# GPS.net
KiCad netlist of a schematic drawn in Altium Designer
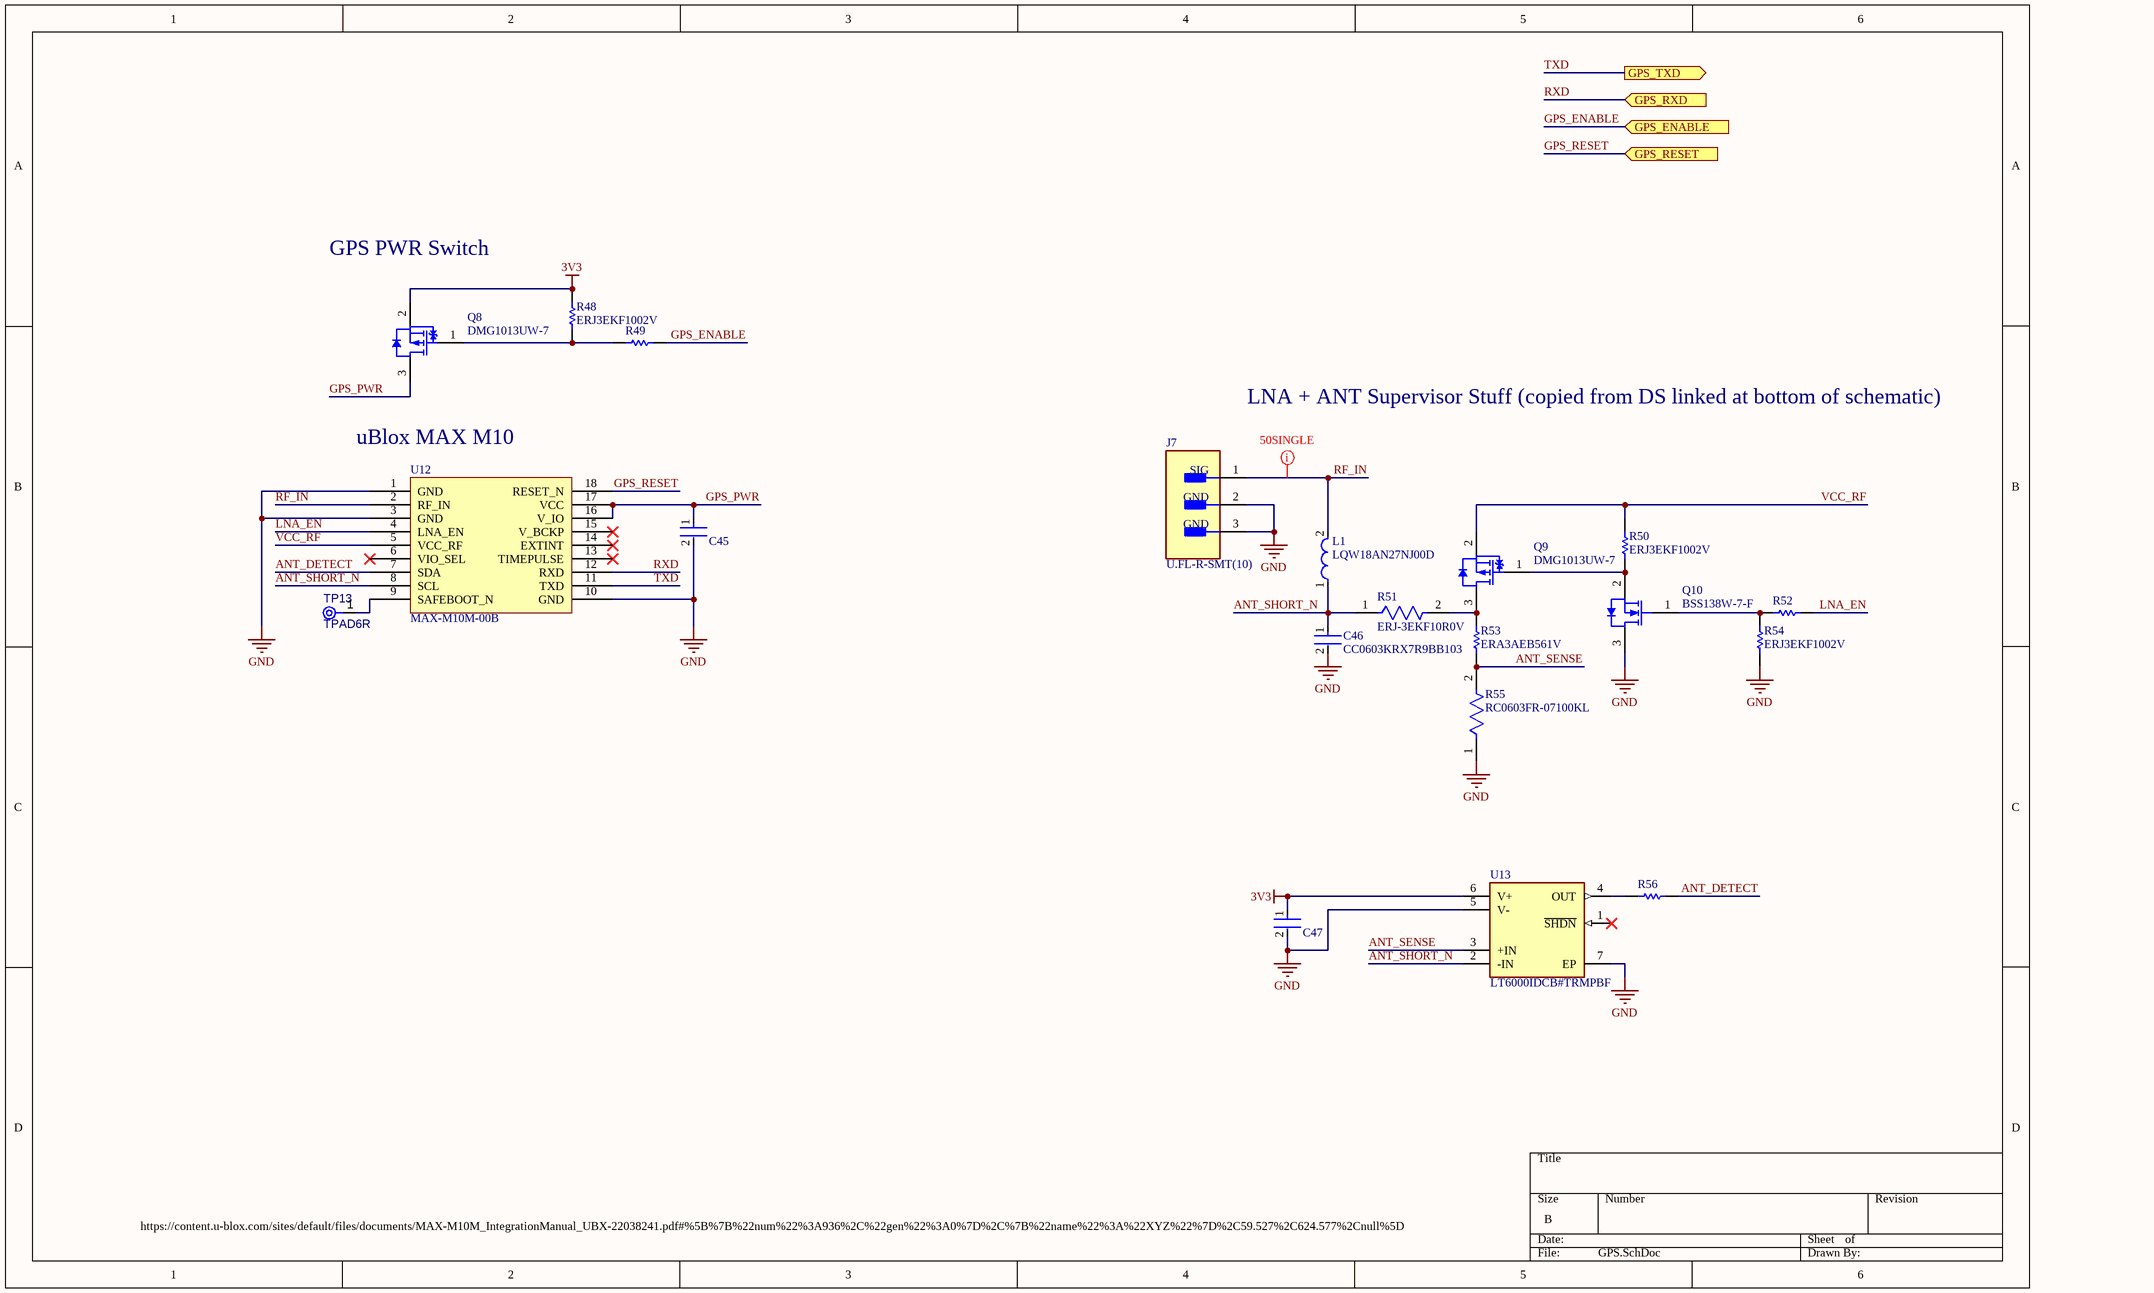
[diagram p0: GPS.SchDoc]

(export (version "E")
  (design (tool "Eeschema 10.0.6"))
  (components
    (comp (ref "C45")
      (value "C0402C104K8PACTU")
      (footprint "FP-C0402-BB-MFG")
      (description "CAP CER 0.1UF 10V X5R 0402")
      (fields (field (name "MANUFACTURER") "Kemet") (field (name "TOLERANCE") "0.1"))
      (libsource (lib "Altium Content Vault") (part "b4654b650e69147ec39a6b967a45e02"))
    )
    (comp (ref "C46")
      (value "CC0603KRX7R9BB103")
      (footprint "FP-CC0603-DA-MFG")
      (description "CAP CER 10000PF 50V X7R 0603")
      (fields (field (name "TOLERANCE") "0.1") (field (name "MANUFACTURER") "YAGEO"))
      (libsource (lib "Altium Content Vault") (part "11868f565c42a9108669ba33697ecf6"))
    )
    (comp (ref "C47")
      (value "C0402C104K8PACTU")
      (footprint "FP-C0402-BB-MFG")
      (description "CAP CER 0.1UF 10V X5R 0402")
      (fields (field (name "MANUFACTURER") "Kemet") (field (name "TOLERANCE") "0.1"))
      (libsource (lib "Altium Content Vault") (part "b4654b650e69147ec39a6b967a45e02"))
    )
    (comp (ref "J7")
      (value "U.FL-R-SMT(10)")
      (footprint "FP-U_FL-R-SMT_10-MFG")
      (description "CONN U.FL RCPT STR 50 OHM SMD")
      (libsource (lib "Altium Content Vault") (part "eef6fde44c591823e8076210edfe12f"))
    )
    (comp (ref "L1")
      (value "LQW18AN27NJ00D")
      (footprint "FP-LQW18AN_00-MFG")
      (description "Wire Wound RF Inductor 27nH ±5% 440mA 0.21Ω 0603 (1608)")
      (fields (field (name "TOLERANCE") "5%"))
      (libsource (lib "Altium Content Vault") (part "725321dda6339637d4d059423bc1c3c"))
    )
    (comp (ref "Q8")
      (value "DMG1013UW-7")
      (footprint "DIOD-SOT323-3_V")
      (fields (field (name "MANUFACTURER") "Diodes Inc"))
      (libsource (lib "Altium Content Vault") (part "PEMOS-GSD-3_C"))
    )
    (comp (ref "Q9")
      (value "DMG1013UW-7")
      (footprint "DIOD-SOT323-3_V")
      (fields (field (name "MANUFACTURER") "Diodes Inc"))
      (libsource (lib "Altium Content Vault") (part "PEMOS-GSD-3_C"))
    )
    (comp (ref "Q10")
      (value "BSS138W-7-F")
      (footprint "DIOD-SOT323-3_V")
      (fields (field (name "MANUFACTURER") "DiodesIncorporated"))
      (libsource (lib "Altium Content Vault") (part "NEMOS-GSD-3"))
    )
    (comp (ref "R48")
      (value "ERJ3EKF1002V")
      (footprint "RESC1609X55X30LL15T15")
      (description "Chip Resistor, 10 KOhm, +/- 1%, 0.1 W, -55 to 155 degC, 0603 (1608 Metric), RoHS, Tape and Reel")
      (fields (field (name "TOLERANCE") "1%") (field (name "MANUFACTURER") "Panasonic"))
      (libsource (lib "Altium Content Vault") (part "RES-2"))
    )
    (comp (ref "R49")
      (value "ERJ-3EKF1001V")
      (footprint "RESC1608X55X30LL15T15")
      (fields (field (name "MANUFACTURER") "Panasonic"))
      (libsource (lib "Altium Content Vault") (part "RES"))
    )
    (comp (ref "R50")
      (value "ERJ3EKF1002V")
      (footprint "RESC1609X55X30LL15T15")
      (description "Chip Resistor, 10 KOhm, +/- 1%, 0.1 W, -55 to 155 degC, 0603 (1608 Metric), RoHS, Tape and Reel")
      (fields (field (name "TOLERANCE") "1%") (field (name "MANUFACTURER") "Panasonic"))
      (libsource (lib "Altium Content Vault") (part "RES-2"))
    )
    (comp (ref "R51")
      (value "ERJ-3EKF10R0V")
      (footprint "FP-ERJ3EK-MFG")
      (description "RES SMD 10 OHM 1% 1/10W 0603")
      (fields
        (field (name "OCTOPART") "https://octopart.com/erj-3ekf10r0v-panasonic-55403649")
        (field (name "MANUFACTURER") "Panasonic")
      )
      (libsource (lib "Altium Content Vault") (part "1029c3af85768c4190bb7ad29bc67b5"))
    )
    (comp (ref "R52")
      (value "ERJ-3EKF1001V")
      (footprint "RESC1608X55X30LL15T15")
      (fields (field (name "MANUFACTURER") "Panasonic"))
      (libsource (lib "Altium Content Vault") (part "RES"))
    )
    (comp (ref "R53")
      (value "ERA3AEB561V")
      (footprint "RESC1608X55X30LL20T20")
      (fields (field (name "MANUFACTURER") "Panasonic"))
      (libsource (lib "Altium Content Vault") (part "RES"))
    )
    (comp (ref "R54")
      (value "ERJ3EKF1002V")
      (footprint "RESC1609X55X30LL15T15")
      (description "Chip Resistor, 10 KOhm, +/- 1%, 0.1 W, -55 to 155 degC, 0603 (1608 Metric), RoHS, Tape and Reel")
      (fields (field (name "TOLERANCE") "1%") (field (name "MANUFACTURER") "Panasonic"))
      (libsource (lib "Altium Content Vault") (part "RES-2"))
    )
    (comp (ref "R55")
      (value "RC0603FR-07100KL")
      (footprint "FP-RC0603-0_55-MFG")
      (description "RES SMD 100K OHM 1% 1/10W 0603")
      (fields (field (name "TOLERANCE") "1%"))
      (libsource (lib "Altium Content Vault") (part "1029c3af85768c4190bb7ad29bc67b5"))
    )
    (comp (ref "R56")
      (value "ERJ-3EKF1001V")
      (footprint "RESC1608X55X30LL15T15")
      (fields (field (name "MANUFACTURER") "Panasonic"))
      (libsource (lib "Altium Content Vault") (part "RES"))
    )
    (comp (ref "TP13")
      (value "TPAD6R")
      (footprint "TP06R")
      (description "0.6mm round")
      (libsource (lib "uORocketry Hardware") (part "CMP-001-0001-4"))
    )
    (comp (ref "U12")
      (value "MAX-M10M-00B")
      (footprint "MAX-M10M-00B-Footprint-1")
      (description "Gnss Lcc Rx Mod, Rom, Crystal")
      (libsource (lib "Space Concordia") (part "MAX-M10M-00B"))
    )
    (comp (ref "U13")
      (value "LT6000IDCB#TRMPBF")
      (footprint "FP-DCB-6-05-08-1715-MFG")
      (description "IC OPAMP GP 1 CIRCUIT 6DFN")
      (libsource (lib "Altium Content Vault") (part "33bb285994f2e703f79bf9d86341a8a"))
    )
  )
  (nets
    (net (code "1") (name "/ANT_DETECT") (class "Default")
      (node (ref "R56") (pin "1") (pinfunction "1_1") (pintype "passive"))
      (node (ref "U12") (pin "7") (pinfunction "SDA_7") (pintype "passive"))
    )
    (net (code "2") (name "/ANT_SENSE") (class "Default")
      (node (ref "R53") (pin "1") (pinfunction "1_1") (pintype "passive"))
      (node (ref "R55") (pin "2") (pinfunction "2_2") (pintype "passive"))
      (node (ref "U13") (pin "3") (pinfunction "+IN_3") (pintype "tri_state"))
    )
    (net (code "3") (name "/ANT_SHORT_N") (class "Default")
      (node (ref "C46") (pin "1") (pinfunction "1_1") (pintype "passive"))
      (node (ref "L1") (pin "1") (pinfunction "1_1") (pintype "passive"))
      (node (ref "R51") (pin "1") (pinfunction "1_1") (pintype "passive"))
      (node (ref "U12") (pin "8") (pinfunction "SCL_8") (pintype "passive"))
      (node (ref "U13") (pin "2") (pinfunction "-IN_2") (pintype "tri_state"))
    )
    (net (code "4") (name "/GPS_ENABLE") (class "Default")
      (node (ref "R49") (pin "1") (pinfunction "1_1") (pintype "passive"))
    )
    (net (code "5") (name "/GPS_PWR") (class "Default")
      (node (ref "C45") (pin "1") (pinfunction "1_1") (pintype "passive"))
      (node (ref "Q8") (pin "3") (pinfunction "D_3") (pintype "passive"))
      (node (ref "U12") (pin "16") (pinfunction "V_IO_16") (pintype "passive"))
      (node (ref "U12") (pin "17") (pinfunction "VCC_17") (pintype "passive"))
    )
    (net (code "6") (name "/GPS_RESET") (class "Default")
      (node (ref "U12") (pin "18") (pinfunction "RESET_N_18") (pintype "passive"))
    )
    (net (code "7") (name "/LNA_EN") (class "Default")
      (node (ref "R52") (pin "1") (pinfunction "1_1") (pintype "passive"))
      (node (ref "U12") (pin "4") (pinfunction "LNA_EN_4") (pintype "passive"))
    )
    (net (code "8") (name "/RF_IN") (class "Default")
      (node (ref "J7") (pin "1") (pinfunction "SIG_1") (pintype "passive"))
      (node (ref "L1") (pin "2") (pinfunction "2_2") (pintype "passive"))
      (node (ref "U12") (pin "2") (pinfunction "RF_IN_2") (pintype "passive"))
    )
    (net (code "9") (name "/RXD") (class "Default")
      (node (ref "U12") (pin "12") (pinfunction "RXD_12") (pintype "passive"))
    )
    (net (code "10") (name "/TXD") (class "Default")
      (node (ref "U12") (pin "11") (pinfunction "TXD_11") (pintype "passive"))
    )
    (net (code "11") (name "/VCC_RF") (class "Default")
      (node (ref "Q9") (pin "2") (pinfunction "S_2") (pintype "passive"))
      (node (ref "R50") (pin "2") (pinfunction "2_2") (pintype "passive"))
      (node (ref "U12") (pin "5") (pinfunction "VCC_RF_5") (pintype "passive"))
    )
    (net (code "12") (name "3V3") (class "Default")
      (node (ref "C47") (pin "1") (pinfunction "1_1") (pintype "passive"))
      (node (ref "Q8") (pin "2") (pinfunction "S_2") (pintype "passive"))
      (node (ref "R48") (pin "2") (pinfunction "2_2") (pintype "passive"))
      (node (ref "U13") (pin "6") (pinfunction "V+_6") (pintype "power_in"))
    )
    (net (code "13") (name "GND") (class "Default")
      (node (ref "C45") (pin "2") (pinfunction "2_2") (pintype "passive"))
      (node (ref "C46") (pin "2") (pinfunction "2_2") (pintype "passive"))
      (node (ref "C47") (pin "2") (pinfunction "2_2") (pintype "passive"))
      (node (ref "J7") (pin "2") (pinfunction "GND_2") (pintype "power_in"))
      (node (ref "J7") (pin "3") (pinfunction "GND_3") (pintype "power_in"))
      (node (ref "Q10") (pin "3") (pinfunction "D_3") (pintype "passive"))
      (node (ref "R54") (pin "1") (pinfunction "1_1") (pintype "passive"))
      (node (ref "R55") (pin "1") (pinfunction "1_1") (pintype "passive"))
      (node (ref "U12") (pin "1") (pinfunction "GND_1") (pintype "passive"))
      (node (ref "U12") (pin "10") (pinfunction "GND_10") (pintype "passive"))
      (node (ref "U12") (pin "3") (pinfunction "GND_3") (pintype "passive"))
      (node (ref "U13") (pin "5") (pinfunction "V-_5") (pintype "power_in"))
      (node (ref "U13") (pin "7") (pinfunction "EP_7") (pintype "power_in"))
    )
    (net (code "14") (name "Net-(Q8-G)") (class "Default")
      (node (ref "Q8") (pin "1") (pinfunction "G_1") (pintype "passive"))
      (node (ref "R48") (pin "1") (pinfunction "1_1") (pintype "passive"))
      (node (ref "R49") (pin "2") (pinfunction "2_2") (pintype "passive"))
    )
    (net (code "15") (name "Net-(Q9-D)") (class "Default")
      (node (ref "Q9") (pin "3") (pinfunction "D_3") (pintype "passive"))
      (node (ref "R51") (pin "2") (pinfunction "2_2") (pintype "passive"))
      (node (ref "R53") (pin "2") (pinfunction "2_2") (pintype "passive"))
    )
    (net (code "16") (name "Net-(Q10-G)") (class "Default")
      (node (ref "Q10") (pin "1") (pinfunction "G_1") (pintype "passive"))
      (node (ref "R52") (pin "2") (pinfunction "2_2") (pintype "passive"))
      (node (ref "R54") (pin "2") (pinfunction "2_2") (pintype "passive"))
    )
    (net (code "17") (name "Net-(Q10-S)") (class "Default")
      (node (ref "Q10") (pin "2") (pinfunction "S_2") (pintype "passive"))
      (node (ref "Q9") (pin "1") (pinfunction "G_1") (pintype "passive"))
      (node (ref "R50") (pin "1") (pinfunction "1_1") (pintype "passive"))
    )
    (net (code "18") (name "Net-(TP13-TP)") (class "Default")
      (node (ref "TP13") (pin "1") (pinfunction "TP_1") (pintype "passive"))
      (node (ref "U12") (pin "9") (pinfunction "SAFEBOOT_N_9") (pintype "passive"))
    )
    (net (code "19") (name "Net-(U13-OUT)") (class "Default")
      (node (ref "R56") (pin "2") (pinfunction "2_2") (pintype "passive"))
      (node (ref "U13") (pin "4") (pinfunction "OUT_4") (pintype "output"))
    )
    (net (code "20") (name "unconnected-(U12-EXTINT-Pad14)") (class "Default")
      (node (ref "U12") (pin "14") (pinfunction "EXTINT_14") (pintype "passive+no_connect"))
    )
    (net (code "21") (name "unconnected-(U12-TIMEPULSE-Pad13)") (class "Default")
      (node (ref "U12") (pin "13") (pinfunction "TIMEPULSE_13") (pintype "passive+no_connect"))
    )
    (net (code "22") (name "unconnected-(U12-VIO_SEL-Pad6)") (class "Default")
      (node (ref "U12") (pin "6") (pinfunction "VIO_SEL_6") (pintype "passive+no_connect"))
    )
    (net (code "23") (name "unconnected-(U12-V_BCKP-Pad15)") (class "Default")
      (node (ref "U12") (pin "15") (pinfunction "V_BCKP_15") (pintype "passive+no_connect"))
    )
    (net (code "24") (name "unconnected-(U13-~{SHDN}-Pad1)") (class "Default")
      (node (ref "U13") (pin "1") (pinfunction "~{SHDN}_1") (pintype "input+no_connect"))
    )
  )
)
